# trackduino1309111914.net
KiCad netlist of a schematic drawn in EAGLE
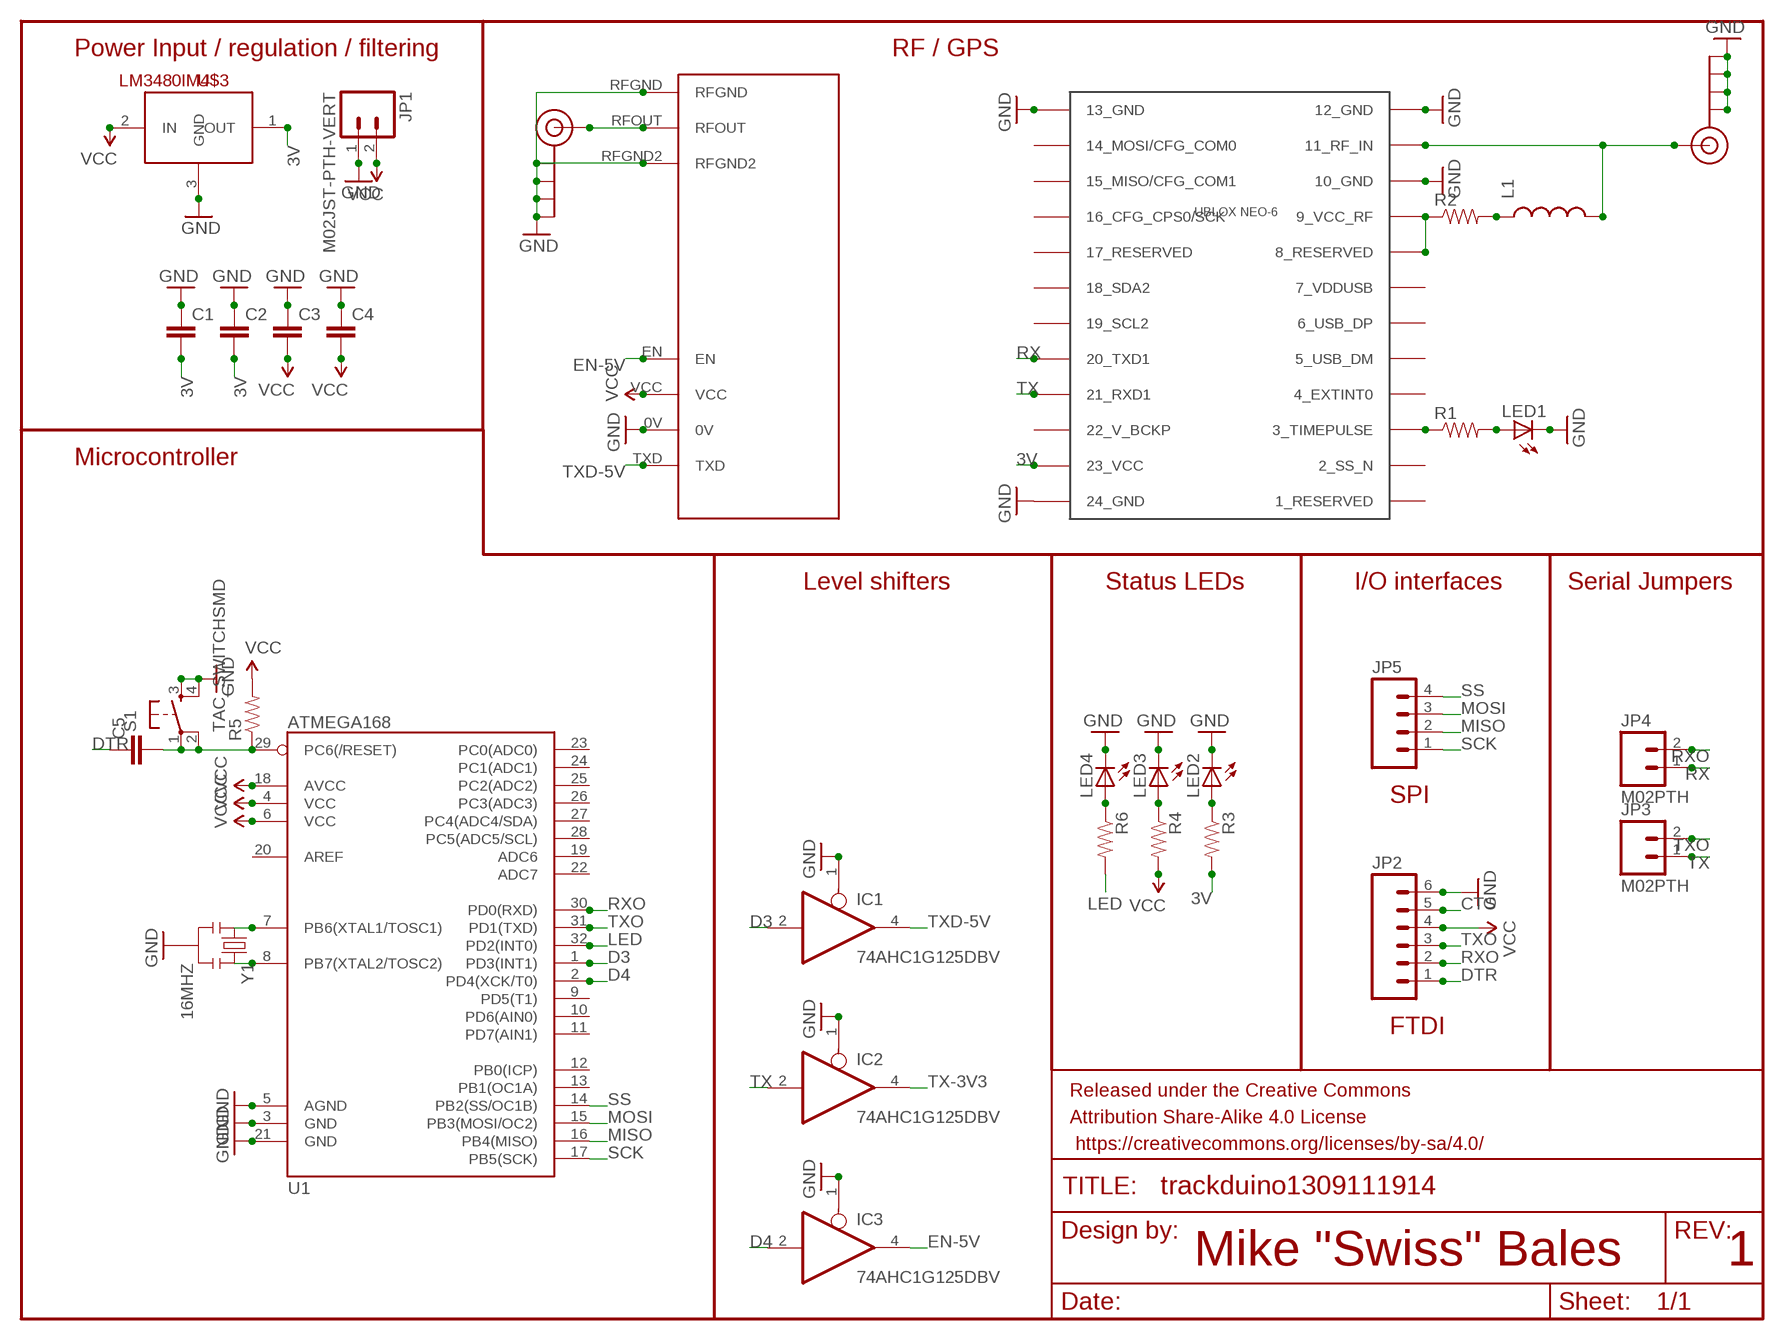
[diagram p0: schematic, sheet 1]

(export (version "E")
  (design (tool "Eeschema 10.0.6"))
  (components
    (comp (ref "C1")
      (value "CAP0805")
      (footprint "eagle-import:0805")
      (libsource (lib "eagle-import") (part "CAP0805"))
    )
    (comp (ref "C2")
      (value "CAP0805")
      (footprint "eagle-import:0805")
      (libsource (lib "eagle-import") (part "CAP0805"))
    )
    (comp (ref "C3")
      (value "CAP0805")
      (footprint "eagle-import:0805")
      (libsource (lib "eagle-import") (part "CAP0805"))
    )
    (comp (ref "C4")
      (value "CAP0805")
      (footprint "eagle-import:0805")
      (libsource (lib "eagle-import") (part "CAP0805"))
    )
    (comp (ref "C5")
      (value "CAP0805")
      (footprint "eagle-import:0805")
      (libsource (lib "eagle-import") (part "CAP0805"))
    )
    (comp (ref "FRAME1")
      (value "FRAME-LETTER")
      (footprint "eagle-import:CREATIVE_COMMONS")
      (libsource (lib "eagle-import") (part "FRAME-LETTER"))
    )
    (comp (ref "IC1")
      (value "74AHC1G125DBV")
      (footprint "eagle-import:SOT23-5")
      (libsource (lib "eagle-import") (part "741G125DBVAHC"))
    )
    (comp (ref "IC2")
      (value "74AHC1G125DBV")
      (footprint "eagle-import:SOT23-5")
      (libsource (lib "eagle-import") (part "741G125DBVAHC"))
    )
    (comp (ref "IC3")
      (value "74AHC1G125DBV")
      (footprint "eagle-import:SOT23-5")
      (libsource (lib "eagle-import") (part "741G125DBVAHC"))
    )
    (comp (ref "J$1")
      (value "SMA_EDGE")
      (footprint "eagle-import:SMA-EDGE")
      (libsource (lib "eagle-import") (part "SMA_EDGE"))
    )
    (comp (ref "J$2")
      (value "SMA_EDGE")
      (footprint "eagle-import:SMA-EDGE")
      (libsource (lib "eagle-import") (part "SMA_EDGE"))
    )
    (comp (ref "JP1")
      (value "M02JST-PTH-VERT")
      (footprint "eagle-import:JST-2-PTH-VERT")
      (libsource (lib "eagle-import") (part "M02JST-PTH-VERT"))
    )
    (comp (ref "JP2")
      (value "M06NO_SILK_FEMALE_PTH")
      (footprint "eagle-import:1X06_NO_SILK")
      (libsource (lib "eagle-import") (part "M06NO_SILK_FEMALE_PTH"))
    )
    (comp (ref "JP3")
      (value "M02PTH")
      (footprint "eagle-import:1X02")
      (libsource (lib "eagle-import") (part "M02PTH"))
    )
    (comp (ref "JP4")
      (value "M02PTH")
      (footprint "eagle-import:1X02")
      (libsource (lib "eagle-import") (part "M02PTH"))
    )
    (comp (ref "JP5")
      (value "M041X04_NO_SILK")
      (footprint "eagle-import:1X04_NO_SILK")
      (libsource (lib "eagle-import") (part "M041X04_NO_SILK"))
    )
    (comp (ref "L1")
      (value "INDUCTOR0805")
      (footprint "eagle-import:0805")
      (libsource (lib "eagle-import") (part "INDUCTOR0805"))
    )
    (comp (ref "LED1")
      (value "LEDCHIP-LED0805")
      (footprint "eagle-import:CHIP-LED0805")
      (libsource (lib "eagle-import") (part "LEDCHIP-LED0805"))
    )
    (comp (ref "LED2")
      (value "LEDCHIP-LED0805")
      (footprint "eagle-import:CHIP-LED0805")
      (libsource (lib "eagle-import") (part "LEDCHIP-LED0805"))
    )
    (comp (ref "LED3")
      (value "LEDCHIP-LED0805")
      (footprint "eagle-import:CHIP-LED0805")
      (libsource (lib "eagle-import") (part "LEDCHIP-LED0805"))
    )
    (comp (ref "LED4")
      (value "LEDCHIP-LED0805")
      (footprint "eagle-import:CHIP-LED0805")
      (libsource (lib "eagle-import") (part "LEDCHIP-LED0805"))
    )
    (comp (ref "R1")
      (value "RESISTOR0805-RES")
      (footprint "eagle-import:0805")
      (libsource (lib "eagle-import") (part "RESISTOR0805-RES"))
    )
    (comp (ref "R2")
      (value "RESISTOR0805-RES")
      (footprint "eagle-import:0805")
      (libsource (lib "eagle-import") (part "RESISTOR0805-RES"))
    )
    (comp (ref "R3")
      (value "RESISTOR0805-RES")
      (footprint "eagle-import:0805")
      (libsource (lib "eagle-import") (part "RESISTOR0805-RES"))
    )
    (comp (ref "R4")
      (value "RESISTOR0805-RES")
      (footprint "eagle-import:0805")
      (libsource (lib "eagle-import") (part "RESISTOR0805-RES"))
    )
    (comp (ref "R5")
      (value "RESISTOR0805-RES")
      (footprint "eagle-import:0805")
      (libsource (lib "eagle-import") (part "RESISTOR0805-RES"))
    )
    (comp (ref "R6")
      (value "RESISTOR0805-RES")
      (footprint "eagle-import:0805")
      (libsource (lib "eagle-import") (part "RESISTOR0805-RES"))
    )
    (comp (ref "S1")
      (value "TAC_SWITCHSMD")
      (footprint "eagle-import:TACTILE-SWITCH-SMD")
      (libsource (lib "eagle-import") (part "TAC_SWITCHSMD"))
    )
    (comp (ref "U$1")
      (value "UBLOX_NEO-6")
      (footprint "eagle-import:UBLOX_NEO-6P")
      (libsource (lib "eagle-import") (part "UBLOX_NEO-6"))
    )
    (comp (ref "U$2")
      (value "RADIOMETRIX-HX1")
      (footprint "eagle-import:RADIOMETRIX-HX1")
      (libsource (lib "eagle-import") (part "RADIOMETRIX-HX1"))
    )
    (comp (ref "U$3")
      (value "LM3480IM4")
      (footprint "eagle-import:SOT23-3")
      (libsource (lib "eagle-import") (part "LM3480IM4"))
    )
    (comp (ref "U1")
      (value "ATMEGA168")
      (footprint "eagle-import:TQFP32-08")
      (libsource (lib "eagle-import") (part "ATMEGA168"))
    )
    (comp (ref "Y1")
      (value "16MHZ")
      (footprint "eagle-import:RESONATOR-SMD")
      (libsource (lib "eagle-import") (part "RESONATOR16MHZ"))
    )
  )
  (nets
    (net (code "1") (name "/3V") (class "Default")
      (node (ref "C1") (pin "2") (pinfunction "2_2") (pintype "passive"))
      (node (ref "C2") (pin "2") (pinfunction "2_2") (pintype "passive"))
      (node (ref "R3") (pin "2") (pinfunction "2_2") (pintype "passive"))
      (node (ref "U$1") (pin "23_VCC") (pinfunction "23_VCC_23_VCC") (pintype "bidirectional"))
      (node (ref "U$3") (pin "1") (pinfunction "OUT_1") (pintype "bidirectional"))
    )
    (net (code "2") (name "/CTS") (class "Default")
      (node (ref "JP2") (pin "5") (pinfunction "5_5") (pintype "passive"))
    )
    (net (code "3") (name "/D3") (class "Default")
      (node (ref "IC1") (pin "2") (pinfunction "I_2") (pintype "input"))
      (node (ref "U1") (pin "1") (pinfunction "PD3(INT1)_1") (pintype "bidirectional"))
    )
    (net (code "4") (name "/D4") (class "Default")
      (node (ref "IC3") (pin "2") (pinfunction "I_2") (pintype "input"))
      (node (ref "U1") (pin "2") (pinfunction "PD4(XCK/T0)_2") (pintype "bidirectional"))
    )
    (net (code "5") (name "/DTR") (class "Default")
      (node (ref "C5") (pin "1") (pinfunction "1_1") (pintype "passive"))
      (node (ref "JP2") (pin "1") (pinfunction "1_1") (pintype "passive"))
    )
    (net (code "6") (name "/EN-5V") (class "Default")
      (node (ref "IC3") (pin "4") (pinfunction "O_4") (pintype "tri_state"))
      (node (ref "U$2") (pin "EN") (pinfunction "EN_EN") (pintype "bidirectional"))
    )
    (net (code "7") (name "/LED") (class "Default")
      (node (ref "R6") (pin "2") (pinfunction "2_2") (pintype "passive"))
      (node (ref "U1") (pin "32") (pinfunction "PD2(INT0)_32") (pintype "bidirectional"))
    )
    (net (code "8") (name "/MISO") (class "Default")
      (node (ref "JP5") (pin "2") (pinfunction "2_2") (pintype "passive"))
      (node (ref "U1") (pin "16") (pinfunction "PB4(MISO)_16") (pintype "bidirectional"))
    )
    (net (code "9") (name "/MOSI") (class "Default")
      (node (ref "JP5") (pin "3") (pinfunction "3_3") (pintype "passive"))
      (node (ref "U1") (pin "15") (pinfunction "PB3(MOSI/OC2)_15") (pintype "bidirectional"))
    )
    (net (code "10") (name "/RX") (class "Default")
      (node (ref "JP4") (pin "1") (pinfunction "1_1") (pintype "passive"))
      (node (ref "U$1") (pin "20_TXD1") (pinfunction "20_TXD1_20_TXD1") (pintype "bidirectional"))
    )
    (net (code "11") (name "/RXO") (class "Default")
      (node (ref "JP2") (pin "2") (pinfunction "2_2") (pintype "passive"))
      (node (ref "JP4") (pin "2") (pinfunction "2_2") (pintype "passive"))
      (node (ref "U1") (pin "30") (pinfunction "PD0(RXD)_30") (pintype "bidirectional"))
    )
    (net (code "12") (name "/SCK") (class "Default")
      (node (ref "JP5") (pin "1") (pinfunction "1_1") (pintype "passive"))
      (node (ref "U1") (pin "17") (pinfunction "PB5(SCK)_17") (pintype "bidirectional"))
    )
    (net (code "13") (name "/SS") (class "Default")
      (node (ref "JP5") (pin "4") (pinfunction "4_4") (pintype "passive"))
      (node (ref "U1") (pin "14") (pinfunction "PB2(SS/OC1B)_14") (pintype "bidirectional"))
    )
    (net (code "14") (name "/TX") (class "Default")
      (node (ref "IC2") (pin "2") (pinfunction "I_2") (pintype "input"))
      (node (ref "JP3") (pin "1") (pinfunction "1_1") (pintype "passive"))
      (node (ref "U$1") (pin "21_RXD1") (pinfunction "21_RXD1_21_RXD1") (pintype "bidirectional"))
    )
    (net (code "15") (name "/TX-3V3") (class "Default")
      (node (ref "IC2") (pin "4") (pinfunction "O_4") (pintype "tri_state"))
    )
    (net (code "16") (name "/TXD-5V") (class "Default")
      (node (ref "IC1") (pin "4") (pinfunction "O_4") (pintype "tri_state"))
      (node (ref "U$2") (pin "TXD") (pinfunction "TXD_TXD") (pintype "bidirectional"))
    )
    (net (code "17") (name "/TXO") (class "Default")
      (node (ref "JP2") (pin "3") (pinfunction "3_3") (pintype "passive"))
      (node (ref "JP3") (pin "2") (pinfunction "2_2") (pintype "passive"))
      (node (ref "U1") (pin "31") (pinfunction "PD1(TXD)_31") (pintype "bidirectional"))
    )
    (net (code "18") (name "GND") (class "Default")
      (node (ref "C1") (pin "1") (pinfunction "1_1") (pintype "passive"))
      (node (ref "C2") (pin "1") (pinfunction "1_1") (pintype "passive"))
      (node (ref "C3") (pin "1") (pinfunction "1_1") (pintype "passive"))
      (node (ref "C4") (pin "1") (pinfunction "1_1") (pintype "passive"))
      (node (ref "IC1") (pin "1") (pinfunction "OE_1") (pintype "input"))
      (node (ref "IC2") (pin "1") (pinfunction "OE_1") (pintype "input"))
      (node (ref "IC3") (pin "1") (pinfunction "OE_1") (pintype "input"))
      (node (ref "J$1") (pin "GND@0") (pinfunction "GND_GND@0") (pintype "bidirectional"))
      (node (ref "J$1") (pin "GND@1") (pinfunction "GND_GND@1") (pintype "bidirectional"))
      (node (ref "J$1") (pin "GND@2") (pinfunction "GND_GND@2") (pintype "bidirectional"))
      (node (ref "J$1") (pin "GND@3") (pinfunction "GND_GND@3") (pintype "bidirectional"))
      (node (ref "J$2") (pin "GND@0") (pinfunction "GND_GND@0") (pintype "bidirectional"))
      (node (ref "J$2") (pin "GND@1") (pinfunction "GND_GND@1") (pintype "bidirectional"))
      (node (ref "J$2") (pin "GND@2") (pinfunction "GND_GND@2") (pintype "bidirectional"))
      (node (ref "J$2") (pin "GND@3") (pinfunction "GND_GND@3") (pintype "bidirectional"))
      (node (ref "JP1") (pin "1") (pinfunction "1_1") (pintype "passive"))
      (node (ref "JP2") (pin "6") (pinfunction "6_6") (pintype "passive"))
      (node (ref "LED1") (pin "C") (pinfunction "C_C") (pintype "passive"))
      (node (ref "LED2") (pin "C") (pinfunction "C_C") (pintype "passive"))
      (node (ref "LED3") (pin "C") (pinfunction "C_C") (pintype "passive"))
      (node (ref "LED4") (pin "C") (pinfunction "C_C") (pintype "passive"))
      (node (ref "S1") (pin "3") (pinfunction "3_3") (pintype "passive"))
      (node (ref "S1") (pin "4") (pinfunction "4_4") (pintype "passive"))
      (node (ref "U$1") (pin "10_GND") (pinfunction "10_GND_10_GND") (pintype "bidirectional"))
      (node (ref "U$1") (pin "12_GND") (pinfunction "12_GND_12_GND") (pintype "bidirectional"))
      (node (ref "U$1") (pin "13_GND") (pinfunction "13_GND_13_GND") (pintype "bidirectional"))
      (node (ref "U$1") (pin "24_GND") (pinfunction "24_GND_24_GND") (pintype "bidirectional"))
      (node (ref "U$2") (pin "0V") (pinfunction "0V_0V") (pintype "bidirectional"))
      (node (ref "U$2") (pin "RFGND") (pinfunction "RFGND_RFGND") (pintype "bidirectional"))
      (node (ref "U$2") (pin "RFGND2") (pinfunction "RFGND2_RFGND2") (pintype "bidirectional"))
      (node (ref "U$3") (pin "3") (pinfunction "GND_3") (pintype "bidirectional"))
      (node (ref "U1") (pin "21") (pinfunction "GND_21") (pintype "bidirectional"))
      (node (ref "U1") (pin "3") (pinfunction "GND_3") (pintype "bidirectional"))
      (node (ref "U1") (pin "5") (pinfunction "AGND_5") (pintype "bidirectional"))
      (node (ref "Y1") (pin "2") (pinfunction "2_2") (pintype "passive"))
    )
    (net (code "19") (name "Net-(J$1-SIGNAL)") (class "Default")
      (node (ref "J$1") (pin "SIG") (pinfunction "SIGNAL_SIG") (pintype "bidirectional"))
      (node (ref "U$2") (pin "RFOUT") (pinfunction "RFOUT_RFOUT") (pintype "bidirectional"))
    )
    (net (code "20") (name "Net-(J$2-SIGNAL)") (class "Default")
      (node (ref "J$2") (pin "SIG") (pinfunction "SIGNAL_SIG") (pintype "bidirectional"))
      (node (ref "L1") (pin "2") (pinfunction "2_2") (pintype "passive"))
      (node (ref "U$1") (pin "11_RF_IN") (pinfunction "11_RF_IN_11_RF_IN") (pintype "bidirectional"))
    )
    (net (code "21") (name "Net-(L1-Pad1)") (class "Default")
      (node (ref "L1") (pin "1") (pinfunction "1_1") (pintype "passive"))
      (node (ref "R2") (pin "2") (pinfunction "2_2") (pintype "passive"))
    )
    (net (code "22") (name "Net-(LED1-PadA)") (class "Default")
      (node (ref "LED1") (pin "A") (pinfunction "A_A") (pintype "passive"))
      (node (ref "R1") (pin "2") (pinfunction "2_2") (pintype "passive"))
    )
    (net (code "23") (name "Net-(LED2-PadA)") (class "Default")
      (node (ref "LED2") (pin "A") (pinfunction "A_A") (pintype "passive"))
      (node (ref "R3") (pin "1") (pinfunction "1_1") (pintype "passive"))
    )
    (net (code "24") (name "Net-(LED3-PadA)") (class "Default")
      (node (ref "LED3") (pin "A") (pinfunction "A_A") (pintype "passive"))
      (node (ref "R4") (pin "1") (pinfunction "1_1") (pintype "passive"))
    )
    (net (code "25") (name "Net-(LED4-PadA)") (class "Default")
      (node (ref "LED4") (pin "A") (pinfunction "A_A") (pintype "passive"))
      (node (ref "R6") (pin "1") (pinfunction "1_1") (pintype "passive"))
    )
    (net (code "26") (name "Net-(R1-Pad1)") (class "Default")
      (node (ref "R1") (pin "1") (pinfunction "1_1") (pintype "passive"))
      (node (ref "U$1") (pin "3_TIMEPULSE") (pinfunction "3_TIMEPULSE_3_TIMEPULSE") (pintype "bidirectional"))
    )
    (net (code "27") (name "Net-(R2-Pad1)") (class "Default")
      (node (ref "R2") (pin "1") (pinfunction "1_1") (pintype "passive"))
      (node (ref "U$1") (pin "8_RESERVED") (pinfunction "8_RESERVED_8_RESERVED") (pintype "bidirectional"))
      (node (ref "U$1") (pin "9_VCC_RF") (pinfunction "9_VCC_RF_9_VCC_RF") (pintype "bidirectional"))
    )
    (net (code "28") (name "Net-(U1-PB6(XTAL1{slash}TOSC1))") (class "Default")
      (node (ref "U1") (pin "7") (pinfunction "PB6(XTAL1/TOSC1)_7") (pintype "bidirectional"))
      (node (ref "Y1") (pin "1") (pinfunction "1_1") (pintype "passive"))
    )
    (net (code "29") (name "Net-(U1-PB7(XTAL2{slash}TOSC2))") (class "Default")
      (node (ref "U1") (pin "8") (pinfunction "PB7(XTAL2/TOSC2)_8") (pintype "bidirectional"))
      (node (ref "Y1") (pin "3") (pinfunction "3_3") (pintype "passive"))
    )
    (net (code "30") (name "Net-(U1-PC6({slash}RESET))") (class "Default")
      (node (ref "C5") (pin "2") (pinfunction "2_2") (pintype "passive"))
      (node (ref "R5") (pin "1") (pinfunction "1_1") (pintype "passive"))
      (node (ref "S1") (pin "1") (pinfunction "1_1") (pintype "passive"))
      (node (ref "S1") (pin "2") (pinfunction "2_2") (pintype "passive"))
      (node (ref "U1") (pin "29") (pinfunction "PC6(/RESET)_29") (pintype "bidirectional"))
    )
    (net (code "31") (name "VCC") (class "Default")
      (node (ref "C3") (pin "2") (pinfunction "2_2") (pintype "passive"))
      (node (ref "C4") (pin "2") (pinfunction "2_2") (pintype "passive"))
      (node (ref "JP1") (pin "2") (pinfunction "2_2") (pintype "passive"))
      (node (ref "JP2") (pin "4") (pinfunction "4_4") (pintype "passive"))
      (node (ref "R4") (pin "2") (pinfunction "2_2") (pintype "passive"))
      (node (ref "R5") (pin "2") (pinfunction "2_2") (pintype "passive"))
      (node (ref "U$2") (pin "VCC") (pinfunction "VCC_VCC") (pintype "bidirectional"))
      (node (ref "U$3") (pin "2") (pinfunction "IN_2") (pintype "bidirectional"))
      (node (ref "U1") (pin "18") (pinfunction "AVCC_18") (pintype "bidirectional"))
      (node (ref "U1") (pin "4") (pinfunction "VCC_4") (pintype "bidirectional"))
      (node (ref "U1") (pin "6") (pinfunction "VCC_6") (pintype "bidirectional"))
    )
    (net (code "32") (name "unconnected-(U$1-Pad1_RESERVED)") (class "Default")
      (node (ref "U$1") (pin "1_RESERVED") (pinfunction "1_RESERVED_1_RESERVED") (pintype "bidirectional"))
    )
    (net (code "33") (name "unconnected-(U$1-Pad2_SS_N)") (class "Default")
      (node (ref "U$1") (pin "2_SS_N") (pinfunction "2_SS_N_2_SS_N") (pintype "bidirectional"))
    )
    (net (code "34") (name "unconnected-(U$1-Pad4_EXTINT0)") (class "Default")
      (node (ref "U$1") (pin "4_EXTINT0") (pinfunction "4_EXTINT0_4_EXTINT0") (pintype "bidirectional"))
    )
    (net (code "35") (name "unconnected-(U$1-Pad5_USB_DM)") (class "Default")
      (node (ref "U$1") (pin "5_USB_DM") (pinfunction "5_USB_DM_5_USB_DM") (pintype "bidirectional"))
    )
    (net (code "36") (name "unconnected-(U$1-Pad6_USB_DP)") (class "Default")
      (node (ref "U$1") (pin "6_USB_DP") (pinfunction "6_USB_DP_6_USB_DP") (pintype "bidirectional"))
    )
    (net (code "37") (name "unconnected-(U$1-Pad7_VDDUSB)") (class "Default")
      (node (ref "U$1") (pin "7_VDDUSB") (pinfunction "7_VDDUSB_7_VDDUSB") (pintype "bidirectional"))
    )
    (net (code "38") (name "unconnected-(U$1-Pad14_MOSI{slash}CFG_COM0)") (class "Default")
      (node (ref "U$1") (pin "14_MOSI/CFG_COM0") (pinfunction "14_MOSI/CFG_COM0_14_MOSI/CFG_COM0") (pintype "bidirectional"))
    )
    (net (code "39") (name "unconnected-(U$1-Pad15_MISO{slash}CFG_COM1)") (class "Default")
      (node (ref "U$1") (pin "15_MISO/CFG_COM1") (pinfunction "15_MISO/CFG_COM1_15_MISO/CFG_COM1") (pintype "bidirectional"))
    )
    (net (code "40") (name "unconnected-(U$1-Pad16_CFG_CPS0{slash}SCK)") (class "Default")
      (node (ref "U$1") (pin "16_CFG_CPS0/SCK") (pinfunction "16_CFG_CPS0/SCK_16_CFG_CPS0/SCK") (pintype "bidirectional"))
    )
    (net (code "41") (name "unconnected-(U$1-Pad17_RESERVED)") (class "Default")
      (node (ref "U$1") (pin "17_RESERVED") (pinfunction "17_RESERVED_17_RESERVED") (pintype "bidirectional"))
    )
    (net (code "42") (name "unconnected-(U$1-Pad18_SDA2)") (class "Default")
      (node (ref "U$1") (pin "18_SDA2") (pinfunction "18_SDA2_18_SDA2") (pintype "bidirectional"))
    )
    (net (code "43") (name "unconnected-(U$1-Pad19_SCL2)") (class "Default")
      (node (ref "U$1") (pin "19_SCL2") (pinfunction "19_SCL2_19_SCL2") (pintype "bidirectional"))
    )
    (net (code "44") (name "unconnected-(U$1-Pad22_V_BCKP)") (class "Default")
      (node (ref "U$1") (pin "22_V_BCKP") (pinfunction "22_V_BCKP_22_V_BCKP") (pintype "bidirectional"))
    )
    (net (code "45") (name "unconnected-(U1-ADC6-Pad19)") (class "Default")
      (node (ref "U1") (pin "19") (pinfunction "ADC6_19") (pintype "bidirectional"))
    )
    (net (code "46") (name "unconnected-(U1-ADC7-Pad22)") (class "Default")
      (node (ref "U1") (pin "22") (pinfunction "ADC7_22") (pintype "bidirectional"))
    )
    (net (code "47") (name "unconnected-(U1-AREF-Pad20)") (class "Default")
      (node (ref "U1") (pin "20") (pinfunction "AREF_20") (pintype "bidirectional"))
    )
    (net (code "48") (name "unconnected-(U1-PB0(ICP)-Pad12)") (class "Default")
      (node (ref "U1") (pin "12") (pinfunction "PB0(ICP)_12") (pintype "bidirectional"))
    )
    (net (code "49") (name "unconnected-(U1-PB1(OC1A)-Pad13)") (class "Default")
      (node (ref "U1") (pin "13") (pinfunction "PB1(OC1A)_13") (pintype "bidirectional"))
    )
    (net (code "50") (name "unconnected-(U1-PC0(ADC0)-Pad23)") (class "Default")
      (node (ref "U1") (pin "23") (pinfunction "PC0(ADC0)_23") (pintype "bidirectional"))
    )
    (net (code "51") (name "unconnected-(U1-PC1(ADC1)-Pad24)") (class "Default")
      (node (ref "U1") (pin "24") (pinfunction "PC1(ADC1)_24") (pintype "bidirectional"))
    )
    (net (code "52") (name "unconnected-(U1-PC2(ADC2)-Pad25)") (class "Default")
      (node (ref "U1") (pin "25") (pinfunction "PC2(ADC2)_25") (pintype "bidirectional"))
    )
    (net (code "53") (name "unconnected-(U1-PC3(ADC3)-Pad26)") (class "Default")
      (node (ref "U1") (pin "26") (pinfunction "PC3(ADC3)_26") (pintype "bidirectional"))
    )
    (net (code "54") (name "unconnected-(U1-PC4(ADC4{slash}SDA)-Pad27)") (class "Default")
      (node (ref "U1") (pin "27") (pinfunction "PC4(ADC4/SDA)_27") (pintype "bidirectional"))
    )
    (net (code "55") (name "unconnected-(U1-PC5(ADC5{slash}SCL)-Pad28)") (class "Default")
      (node (ref "U1") (pin "28") (pinfunction "PC5(ADC5/SCL)_28") (pintype "bidirectional"))
    )
    (net (code "56") (name "unconnected-(U1-PD5(T1)-Pad9)") (class "Default")
      (node (ref "U1") (pin "9") (pinfunction "PD5(T1)_9") (pintype "bidirectional"))
    )
    (net (code "57") (name "unconnected-(U1-PD6(AIN0)-Pad10)") (class "Default")
      (node (ref "U1") (pin "10") (pinfunction "PD6(AIN0)_10") (pintype "bidirectional"))
    )
    (net (code "58") (name "unconnected-(U1-PD7(AIN1)-Pad11)") (class "Default")
      (node (ref "U1") (pin "11") (pinfunction "PD7(AIN1)_11") (pintype "bidirectional"))
    )
  )
)
